# low-pass-filter.net
KiCad netlist of a schematic drawn in EAGLE
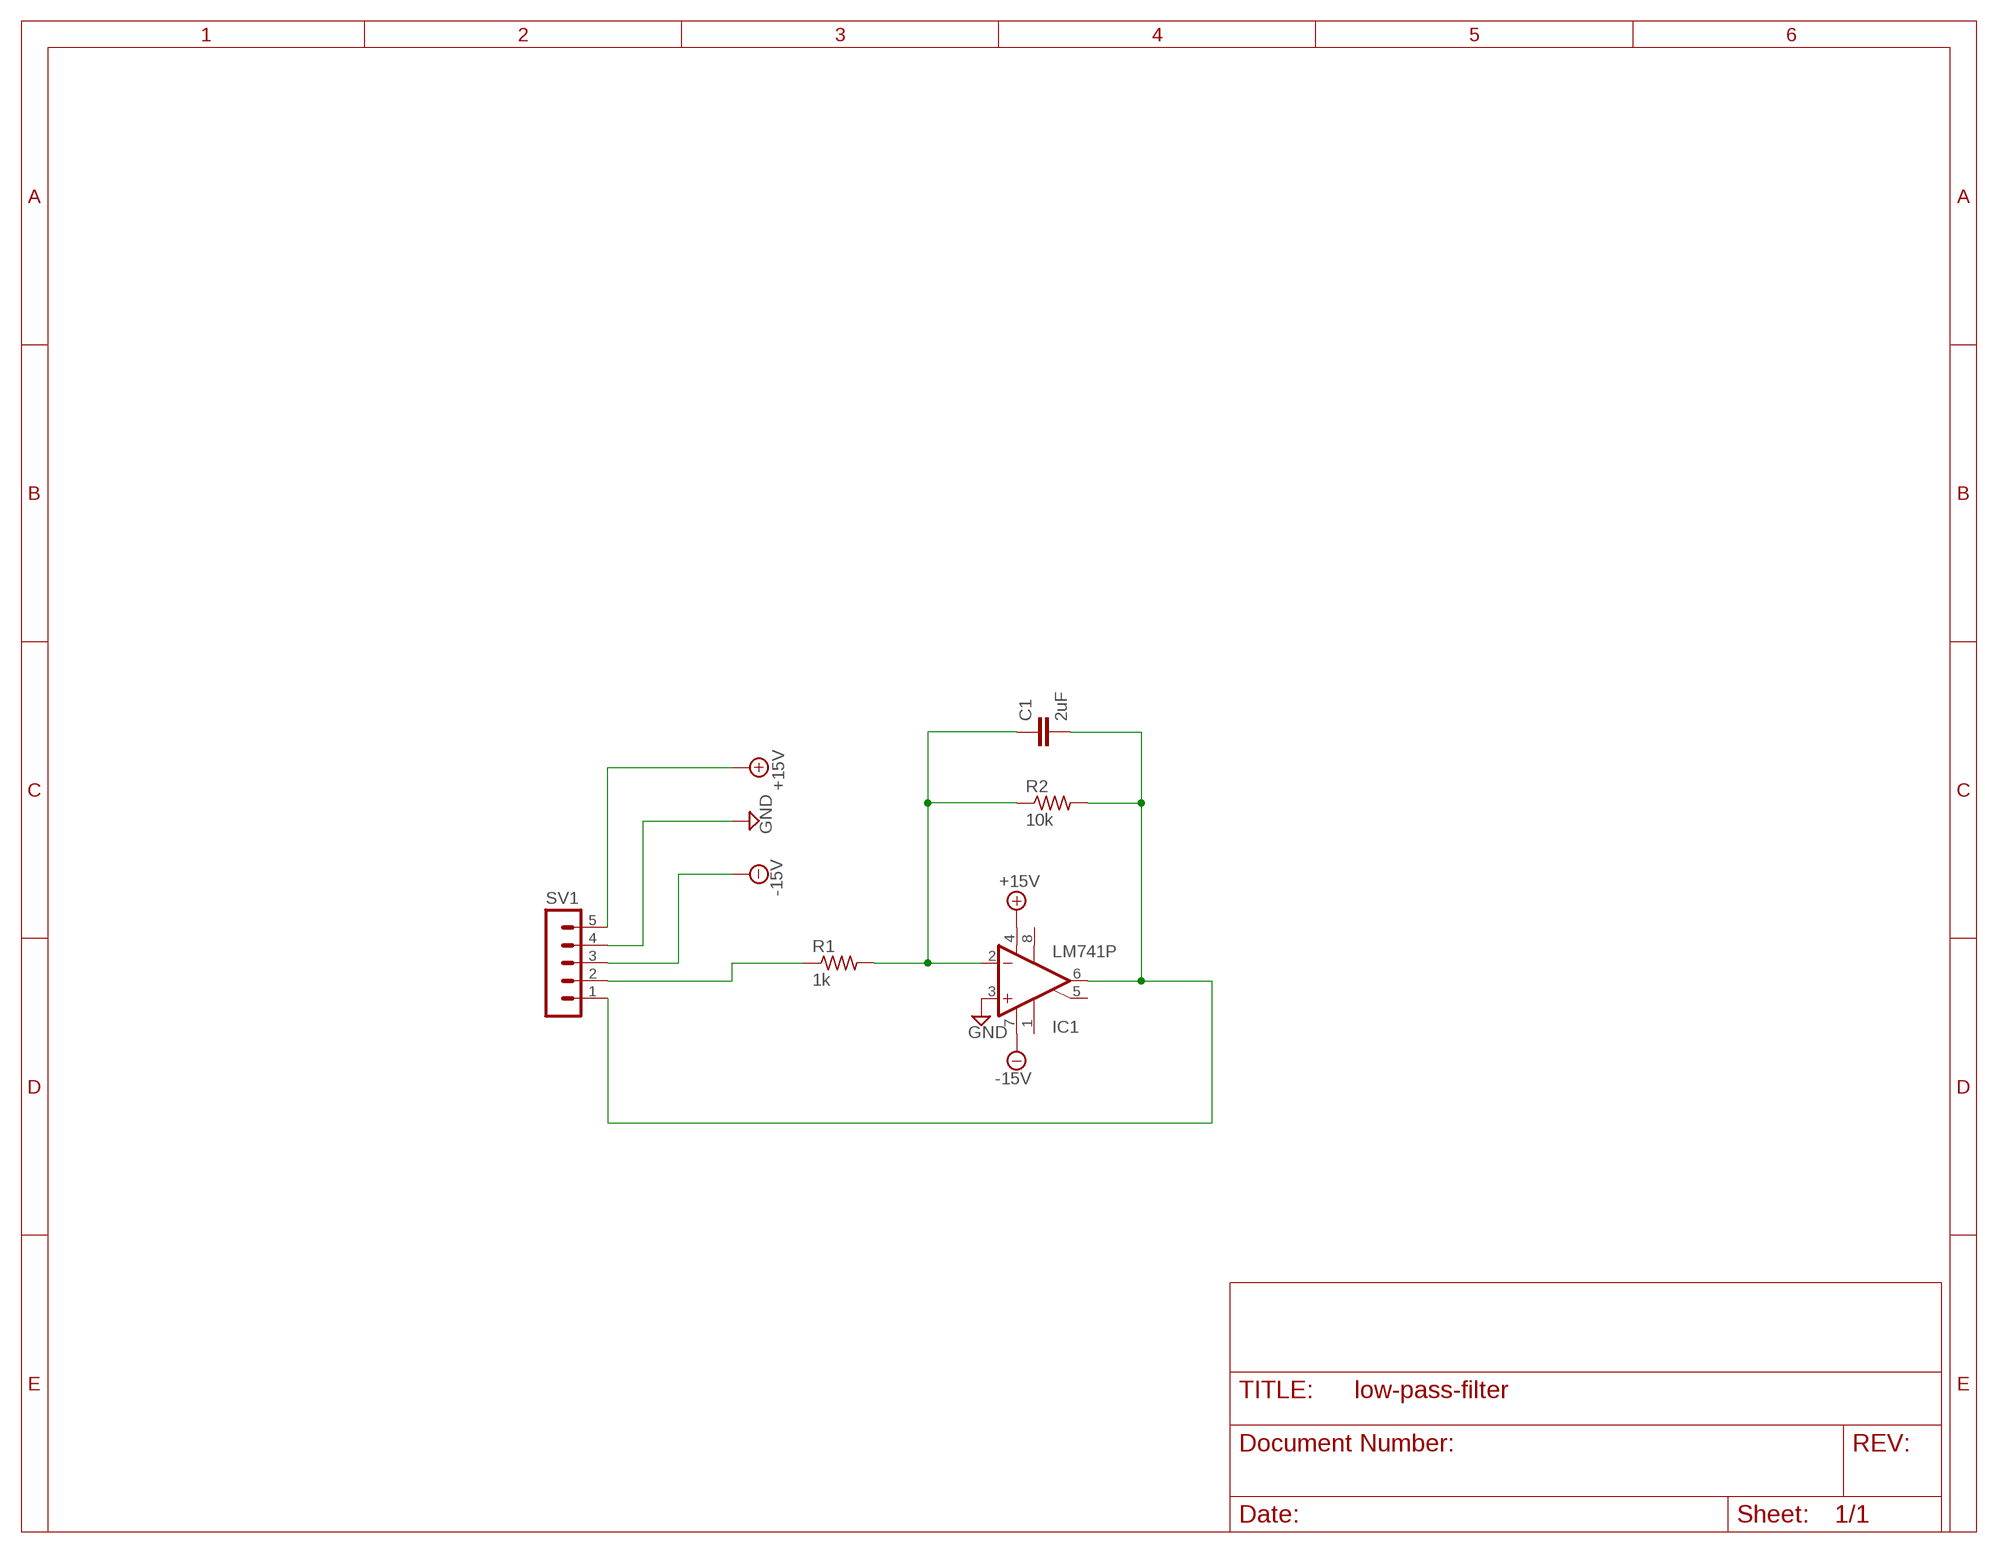
[diagram p0: schematic, sheet 1]

(export (version "E")
  (design (tool "Eeschema 10.0.6"))
  (components
    (comp (ref "C1")
      (value "2uF")
      (footprint "eagle-import:C0603")
      (libsource (lib "eagle-import") (part "C-EUC0603"))
    )
    (comp (ref "IC1")
      (value "LM741P")
      (footprint "eagle-import:DIL08")
      (libsource (lib "eagle-import") (part "741PLM"))
    )
    (comp (ref "R1")
      (value "1k")
      (footprint "eagle-import:R0603")
      (libsource (lib "eagle-import") (part "R-US_R0603"))
    )
    (comp (ref "R2")
      (value "10k")
      (footprint "eagle-import:R0603")
      (libsource (lib "eagle-import") (part "R-US_R0603"))
    )
    (comp (ref "SV1")
      (value "MA05-1")
      (footprint "eagle-import:MA05-1")
      (libsource (lib "eagle-import") (part "MA05-1"))
    )
  )
  (nets
    (net (code "1") (name "+15V") (class "Default")
      (node (ref "IC1") (pin "4") (pinfunction "V-_4") (pintype "power_in"))
      (node (ref "SV1") (pin "5") (pinfunction "5_5") (pintype "passive"))
    )
    (net (code "2") (name "-15V") (class "Default")
      (node (ref "IC1") (pin "7") (pinfunction "V+_7") (pintype "power_in"))
      (node (ref "SV1") (pin "3") (pinfunction "3_3") (pintype "passive"))
    )
    (net (code "3") (name "GND") (class "Default")
      (node (ref "IC1") (pin "3") (pinfunction "+IN_3") (pintype "input"))
      (node (ref "SV1") (pin "4") (pinfunction "4_4") (pintype "passive"))
    )
    (net (code "4") (name "Net-(IC1--IN)") (class "Default")
      (node (ref "C1") (pin "1") (pinfunction "1_1") (pintype "passive"))
      (node (ref "IC1") (pin "2") (pinfunction "-IN_2") (pintype "input"))
      (node (ref "R1") (pin "2") (pinfunction "2_2") (pintype "passive"))
      (node (ref "R2") (pin "1") (pinfunction "1_1") (pintype "passive"))
    )
    (net (code "5") (name "Net-(IC1-OUT)") (class "Default")
      (node (ref "C1") (pin "2") (pinfunction "2_2") (pintype "passive"))
      (node (ref "IC1") (pin "6") (pinfunction "OUT_6") (pintype "output"))
      (node (ref "R2") (pin "2") (pinfunction "2_2") (pintype "passive"))
      (node (ref "SV1") (pin "1") (pinfunction "1_1") (pintype "passive"))
    )
    (net (code "6") (name "Net-(R1-Pad1)") (class "Default")
      (node (ref "R1") (pin "1") (pinfunction "1_1") (pintype "passive"))
      (node (ref "SV1") (pin "2") (pinfunction "2_2") (pintype "passive"))
    )
    (net (code "7") (name "unconnected-(IC1-ON1-Pad1)") (class "Default")
      (node (ref "IC1") (pin "1") (pinfunction "ON1_1") (pintype "passive"))
    )
    (net (code "8") (name "unconnected-(IC1-ON2-Pad5)") (class "Default")
      (node (ref "IC1") (pin "5") (pinfunction "ON2_5") (pintype "passive"))
    )
    (net (code "9") (name "unconnected-(IC1-OPT-Pad8)") (class "Default")
      (node (ref "IC1") (pin "8") (pinfunction "OPT_8") (pintype "passive"))
    )
  )
)
